# DAC.net
KiCad netlist of a schematic drawn in Altium Designer
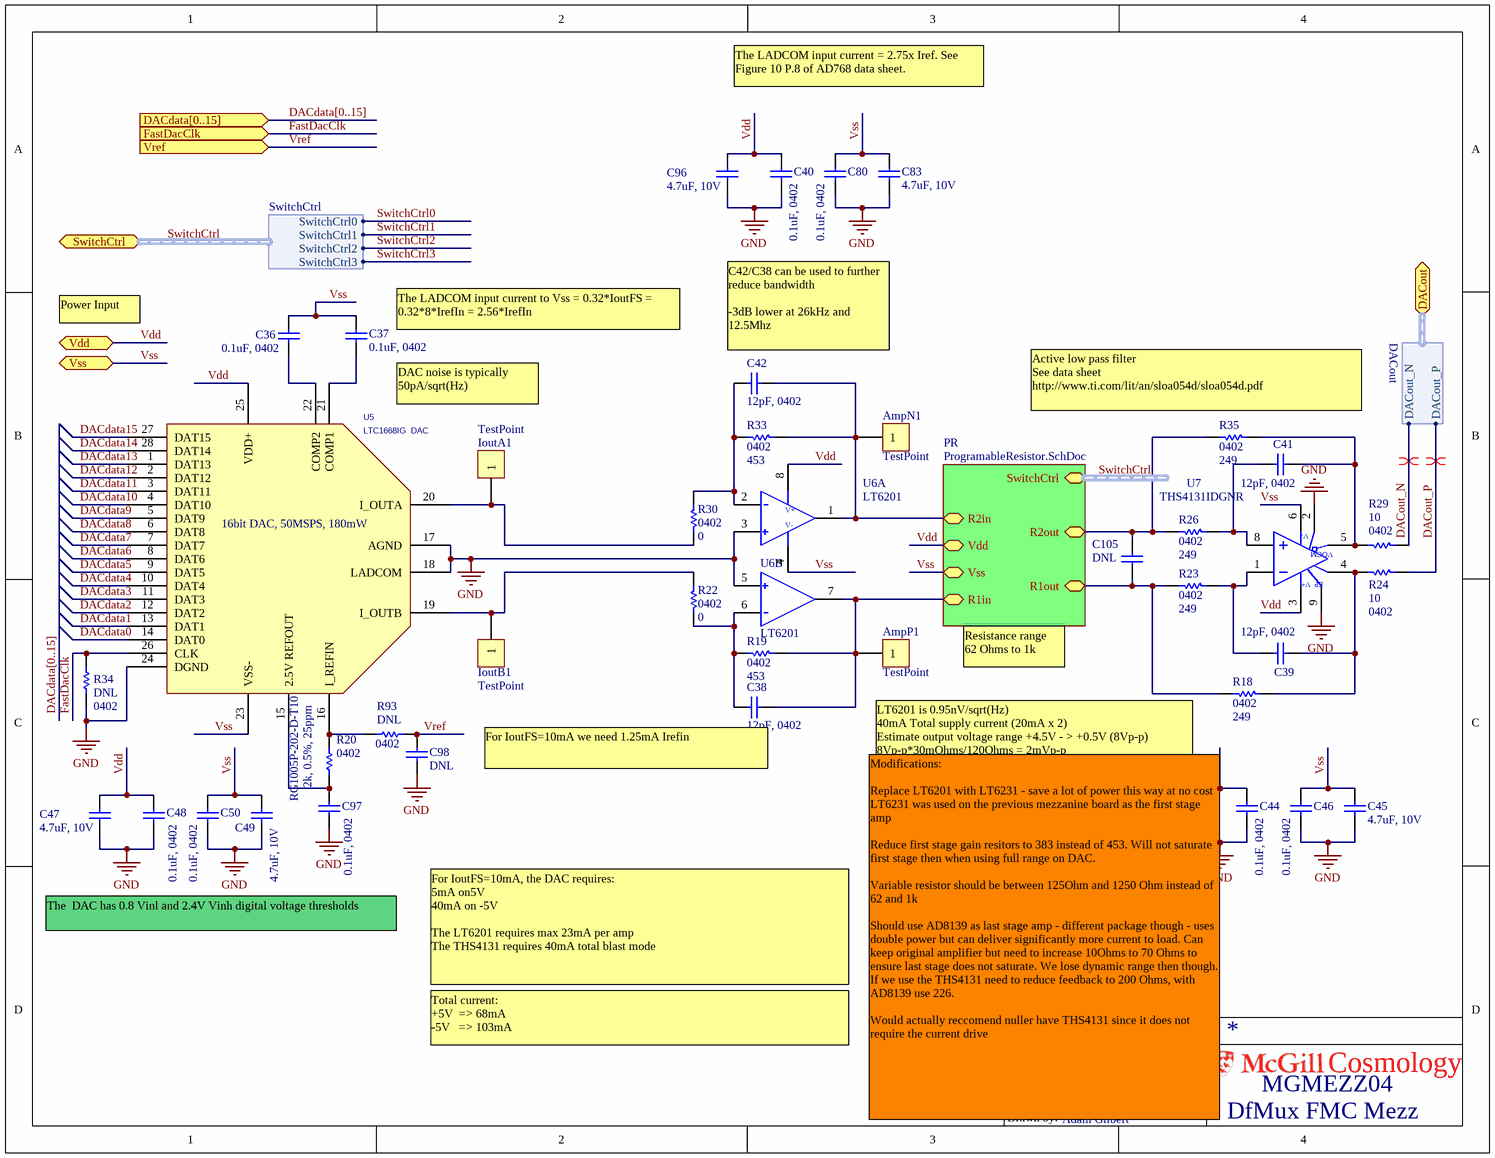
[diagram p0: DAC.SchDoc]

(export (version "E")
  (design (tool "Eeschema 10.0.6"))
  (components
    (comp (ref "AmpN1")
      (value "TestPoint")
      (footprint "TP-3520-SK")
      (description "TestPoint1")
      (libsource (lib "MGMEZZ04") (part "TestPoint"))
    )
    (comp (ref "AmpP1")
      (value "TestPoint")
      (footprint "TP-3520-SK")
      (description "TestPoint1")
      (libsource (lib "MGMEZZ04") (part "TestPoint"))
    )
    (comp (ref "C36")
      (value "0.1uF, 0402")
      (footprint "0402")
      (description "Capacitor, Ceramic, 0402")
      (fields (field (name "MANUFACTURER") "TDK Corporation"))
      (libsource (lib "MGMEZZ04") (part "CAP 0603"))
    )
    (comp (ref "C37")
      (value "0.1uF, 0402")
      (footprint "0402")
      (description "Capacitor, Ceramic, 0402")
      (fields (field (name "MANUFACTURER") "TDK Corporation"))
      (libsource (lib "MGMEZZ04") (part "CAP 0603"))
    )
    (comp (ref "C38")
      (value "12pF, 0402")
      (footprint "0402")
      (description "Capacitor, Ceramic, 0402")
      (fields (field (name "MANUFACTURER") "Generic"))
      (libsource (lib "MGMEZZ04") (part "CAP 0402"))
    )
    (comp (ref "C39")
      (value "12pF, 0402")
      (footprint "0402")
      (description "Capacitor, Ceramic, 0402")
      (fields (field (name "MANUFACTURER") "Generic"))
      (libsource (lib "MGMEZZ04") (part "CAP 0402"))
    )
    (comp (ref "C40")
      (value "0.1uF, 0402")
      (footprint "0402")
      (description "Capacitor, Ceramic, 0402")
      (fields (field (name "MANUFACTURER") "TDK Corporation"))
      (libsource (lib "MGMEZZ04") (part "CAP 0603"))
    )
    (comp (ref "C41")
      (value "12pF, 0402")
      (footprint "0402")
      (description "Capacitor, Ceramic, 0402")
      (fields (field (name "MANUFACTURER") "Generic"))
      (libsource (lib "MGMEZZ04") (part "CAP 0402"))
    )
    (comp (ref "C42")
      (value "12pF, 0402")
      (footprint "0402")
      (description "Capacitor, Ceramic, 0402")
      (fields (field (name "MANUFACTURER") "Generic"))
      (libsource (lib "MGMEZZ04") (part "CAP 0402"))
    )
    (comp (ref "C43")
      (value "4.7uF, 10V")
      (footprint "0805")
      (description "Capacitor, Ceramic, 0805")
      (fields (field (name "MANUFACTURER") "Taiyo Yuden"))
      (libsource (lib "MGMEZZ04") (part "CAP 0805"))
    )
    (comp (ref "C44")
      (value "0.1uF, 0402")
      (footprint "0402")
      (description "Capacitor, Ceramic, 0402")
      (fields (field (name "MANUFACTURER") "TDK Corporation"))
      (libsource (lib "MGMEZZ04") (part "CAP 0603"))
    )
    (comp (ref "C45")
      (value "4.7uF, 10V")
      (footprint "0805")
      (description "Capacitor, Ceramic, 0805")
      (fields (field (name "MANUFACTURER") "Taiyo Yuden"))
      (libsource (lib "MGMEZZ04") (part "CAP 0805"))
    )
    (comp (ref "C46")
      (value "0.1uF, 0402")
      (footprint "0402")
      (description "Capacitor, Ceramic, 0402")
      (fields (field (name "MANUFACTURER") "TDK Corporation"))
      (libsource (lib "MGMEZZ04") (part "CAP 0603"))
    )
    (comp (ref "C47")
      (value "4.7uF, 10V")
      (footprint "0805")
      (description "Capacitor, Ceramic, 0805")
      (fields (field (name "MANUFACTURER") "Taiyo Yuden"))
      (libsource (lib "MGMEZZ04") (part "CAP 0805"))
    )
    (comp (ref "C48")
      (value "0.1uF, 0402")
      (footprint "0402")
      (description "Capacitor, Ceramic, 0402")
      (fields (field (name "MANUFACTURER") "TDK Corporation"))
      (libsource (lib "MGMEZZ04") (part "CAP 0603"))
    )
    (comp (ref "C49")
      (value "4.7uF, 10V")
      (footprint "0805")
      (description "Capacitor, Ceramic, 0805")
      (fields (field (name "MANUFACTURER") "Taiyo Yuden"))
      (libsource (lib "MGMEZZ04") (part "CAP 0805"))
    )
    (comp (ref "C50")
      (value "0.1uF, 0402")
      (footprint "0402")
      (description "Capacitor, Ceramic, 0402")
      (fields (field (name "MANUFACTURER") "TDK Corporation"))
      (libsource (lib "MGMEZZ04") (part "CAP 0603"))
    )
    (comp (ref "C80")
      (value "0.1uF, 0402")
      (footprint "0402")
      (description "Capacitor, Ceramic, 0402")
      (fields (field (name "MANUFACTURER") "TDK Corporation"))
      (libsource (lib "MGMEZZ04") (part "CAP 0603"))
    )
    (comp (ref "C83")
      (value "4.7uF, 10V")
      (footprint "0805")
      (description "Capacitor, Ceramic, 0805")
      (fields (field (name "MANUFACTURER") "Taiyo Yuden"))
      (libsource (lib "MGMEZZ04") (part "CAP 0805"))
    )
    (comp (ref "C96")
      (value "4.7uF, 10V")
      (footprint "0805")
      (description "Capacitor, Ceramic, 0805")
      (fields (field (name "MANUFACTURER") "Taiyo Yuden"))
      (libsource (lib "MGMEZZ04") (part "CAP 0805"))
    )
    (comp (ref "C97")
      (value "0.1uF, 0402")
      (footprint "0402")
      (description "Capacitor, Ceramic, 0402")
      (fields (field (name "MANUFACTURER") "TDK Corporation"))
      (libsource (lib "MGMEZZ04") (part "CAP 0603"))
    )
    (comp (ref "C98")
      (value "DNL")
      (footprint "0805")
      (description "Capacitor, Ceramic, 0805")
      (fields (field (name "MANUFACTURER") "Taiyo Yuden"))
      (libsource (lib "MGMEZZ04") (part "CAP 0805"))
    )
    (comp (ref "C105")
      (value "DNL")
      (footprint "0402")
      (description "Capacitor, Ceramic, 0402")
      (fields (field (name "MANUFACTURER") "Generic"))
      (libsource (lib "MGMEZZ04") (part "CAP 0402"))
    )
    (comp (ref "IoutA1")
      (value "TestPoint")
      (footprint "TP-3520-SK")
      (description "TestPoint1")
      (libsource (lib "MGMEZZ04") (part "TestPoint"))
    )
    (comp (ref "IoutB1")
      (value "TestPoint")
      (footprint "TP-3520-SK")
      (description "TestPoint1")
      (libsource (lib "") (part "TestPoint_1"))
    )
    (comp (ref "R18")
      (value "249")
      (footprint "0402")
      (description "Resistor")
      (fields (field (name "MANUFACTURER") "Generic"))
      (libsource (lib "MGMEZZ04") (part "RES 0402"))
    )
    (comp (ref "R19")
      (value "453")
      (footprint "0402")
      (description "Resistor")
      (fields (field (name "MANUFACTURER") "Generic"))
      (libsource (lib "MGMEZZ04") (part "RES 0402"))
    )
    (comp (ref "R20")
      (value "2k, 0.5%, 25ppm")
      (footprint "0402")
      (description "Resistor")
      (fields
        (field (name "MANUFACTURER") "Susumu")
        (field (name "MANUFACTURER PART NUMBER 1") "RG1005P-202-D-T10")
      )
      (libsource (lib "MGMEZZ04") (part "RES 0402"))
    )
    (comp (ref "R22")
      (value "0")
      (footprint "0402")
      (description "Resistor")
      (fields (field (name "MANUFACTURER") "Generic"))
      (libsource (lib "MGMEZZ04") (part "RES 0402"))
    )
    (comp (ref "R23")
      (value "249")
      (footprint "0402")
      (description "Resistor")
      (fields (field (name "MANUFACTURER") "Generic"))
      (libsource (lib "MGMEZZ04") (part "RES 0402"))
    )
    (comp (ref "R24")
      (value "10")
      (footprint "0402")
      (description "Resistor")
      (fields (field (name "MANUFACTURER") "Generic"))
      (libsource (lib "MGMEZZ04") (part "RES 0402"))
    )
    (comp (ref "R26")
      (value "249")
      (footprint "0402")
      (description "Resistor")
      (fields (field (name "MANUFACTURER") "Generic"))
      (libsource (lib "MGMEZZ04") (part "RES 0402"))
    )
    (comp (ref "R29")
      (value "10")
      (footprint "0402")
      (description "Resistor")
      (fields (field (name "MANUFACTURER") "Generic"))
      (libsource (lib "MGMEZZ04") (part "RES 0402"))
    )
    (comp (ref "R30")
      (value "0")
      (footprint "0402")
      (description "Resistor")
      (fields (field (name "MANUFACTURER") "Generic"))
      (libsource (lib "MGMEZZ04") (part "RES 0402"))
    )
    (comp (ref "R33")
      (value "453")
      (footprint "0402")
      (description "Resistor")
      (fields (field (name "MANUFACTURER") "Generic"))
      (libsource (lib "MGMEZZ04") (part "RES 0402"))
    )
    (comp (ref "R34")
      (value "DNL")
      (footprint "0402")
      (description "Resistor")
      (fields (field (name "MANUFACTURER") "Generic"))
      (libsource (lib "MGMEZZ04") (part "RES 0402"))
    )
    (comp (ref "R35")
      (value "249")
      (footprint "0402")
      (description "Resistor")
      (fields (field (name "MANUFACTURER") "Generic"))
      (libsource (lib "MGMEZZ04") (part "RES 0402"))
    )
    (comp (ref "R93")
      (value "DNL")
      (footprint "0402")
      (description "Resistor")
      (fields (field (name "MANUFACTURER") "Susumu"))
      (libsource (lib "MGMEZZ04") (part "RES 0402"))
    )
    (comp (ref "U5")
      (value "LTC1668IG  DAC")
      (footprint "SOG.65M/28/WG8.20/L10.16")
      (description "IC DAC 16BIT 50MSPS 28SSOP")
      (fields (field (name "MANUFACTURER") "Linear Technology"))
      (libsource (lib "MGMEZZ04") (part "LTC1668IG  DAC"))
    )
    (comp (ref "U6")
      (value "LT6201")
      (footprint "SO8")
      (description "Dual R-R Opamp Soic 8 165Mhz GBP")
      (fields (field (name "MANUFACTURER") "Linear Technology"))
      (libsource (lib "MGMEZZ04") (part "LT6201"))
    )
    (comp (ref "U7")
      (value "THS4131IDGNR")
      (footprint "SOP8-EP-127P600-8N")
      (description "IC OPAMP DIFF 225MHZ SGL 8MSOP")
      (fields (field (name "MANUFACTURER") "Texas Instruments"))
      (libsource (lib "MGMEZZ04") (part "THS4131IDGNR"))
    )
  )
  (nets
    (net (code "4") (name "/DACdata0") (class "Default")
      (node (ref "U5") (pin "14") (pinfunction "DAT0_14") (pintype "passive"))
    )
    (net (code "5") (name "/DACdata1") (class "Default")
      (node (ref "U5") (pin "13") (pinfunction "DAT1_13") (pintype "passive"))
    )
    (net (code "6") (name "/DACdata2") (class "Default")
      (node (ref "U5") (pin "12") (pinfunction "DAT2_12") (pintype "passive"))
    )
    (net (code "7") (name "/DACdata3") (class "Default")
      (node (ref "U5") (pin "11") (pinfunction "DAT3_11") (pintype "passive"))
    )
    (net (code "8") (name "/DACdata4") (class "Default")
      (node (ref "U5") (pin "10") (pinfunction "DAT4_10") (pintype "passive"))
    )
    (net (code "9") (name "/DACdata5") (class "Default")
      (node (ref "U5") (pin "9") (pinfunction "DAT5_9") (pintype "passive"))
    )
    (net (code "10") (name "/DACdata6") (class "Default")
      (node (ref "U5") (pin "8") (pinfunction "DAT6_8") (pintype "passive"))
    )
    (net (code "11") (name "/DACdata7") (class "Default")
      (node (ref "U5") (pin "7") (pinfunction "DAT7_7") (pintype "passive"))
    )
    (net (code "12") (name "/DACdata8") (class "Default")
      (node (ref "U5") (pin "6") (pinfunction "DAT8_6") (pintype "passive"))
    )
    (net (code "13") (name "/DACdata9") (class "Default")
      (node (ref "U5") (pin "5") (pinfunction "DAT9_5") (pintype "passive"))
    )
    (net (code "14") (name "/DACdata10") (class "Default")
      (node (ref "U5") (pin "4") (pinfunction "DAT10_4") (pintype "passive"))
    )
    (net (code "15") (name "/DACdata11") (class "Default")
      (node (ref "U5") (pin "3") (pinfunction "DAT11_3") (pintype "passive"))
    )
    (net (code "16") (name "/DACdata12") (class "Default")
      (node (ref "U5") (pin "2") (pinfunction "DAT12_2") (pintype "passive"))
    )
    (net (code "17") (name "/DACdata13") (class "Default")
      (node (ref "U5") (pin "1") (pinfunction "DAT13_1") (pintype "passive"))
    )
    (net (code "18") (name "/DACdata14") (class "Default")
      (node (ref "U5") (pin "28") (pinfunction "DAT14_28") (pintype "passive"))
    )
    (net (code "19") (name "/DACdata15") (class "Default")
      (node (ref "U5") (pin "27") (pinfunction "DAT15_27") (pintype "passive"))
    )
    (net (code "21") (name "/DACout_N") (class "Default")
      (node (ref "R29") (pin "2") (pinfunction "2_2") (pintype "passive"))
    )
    (net (code "22") (name "/DACout_P") (class "Default")
      (node (ref "R24") (pin "2") (pinfunction "2_2") (pintype "passive"))
    )
    (net (code "23") (name "/FastDacClk") (class "Default")
      (node (ref "R34") (pin "2") (pinfunction "2_2") (pintype "passive"))
      (node (ref "U5") (pin "26") (pinfunction "CLK_26") (pintype "passive"))
    )
    (net (code "24") (name "/R1in") (class "Default")
      (node (ref "AmpP1") (pin "1") (pinfunction "1_1") (pintype "passive"))
      (node (ref "C38") (pin "1") (pinfunction "1_1") (pintype "passive"))
      (node (ref "R19") (pin "2") (pinfunction "2_2") (pintype "passive"))
      (node (ref "U6") (pin "7") (pinfunction "Out_7") (pintype "passive"))
    )
    (net (code "25") (name "/R1out") (class "Default")
      (node (ref "C105") (pin "2") (pinfunction "2_2") (pintype "passive"))
      (node (ref "R18") (pin "1") (pinfunction "1_1") (pintype "passive"))
      (node (ref "R23") (pin "1") (pinfunction "1_1") (pintype "passive"))
    )
    (net (code "26") (name "/R2in") (class "Default")
      (node (ref "AmpN1") (pin "1") (pinfunction "1_1") (pintype "passive"))
      (node (ref "C42") (pin "1") (pinfunction "1_1") (pintype "passive"))
      (node (ref "R33") (pin "2") (pinfunction "2_2") (pintype "passive"))
      (node (ref "U6") (pin "1") (pinfunction "Out_1") (pintype "passive"))
    )
    (net (code "27") (name "/R2out") (class "Default")
      (node (ref "C105") (pin "1") (pinfunction "1_1") (pintype "passive"))
      (node (ref "R26") (pin "1") (pinfunction "1_1") (pintype "passive"))
      (node (ref "R35") (pin "1") (pinfunction "1_1") (pintype "passive"))
    )
    (net (code "33") (name "/Vdd") (class "Default")
      (node (ref "C40") (pin "2") (pinfunction "2_2") (pintype "passive"))
      (node (ref "C43") (pin "2") (pinfunction "2_2") (pintype "passive"))
      (node (ref "C44") (pin "2") (pinfunction "2_2") (pintype "passive"))
      (node (ref "C47") (pin "2") (pinfunction "2_2") (pintype "passive"))
      (node (ref "C48") (pin "2") (pinfunction "2_2") (pintype "passive"))
      (node (ref "C96") (pin "2") (pinfunction "2_2") (pintype "passive"))
      (node (ref "U5") (pin "25") (pinfunction "VDD+_25") (pintype "passive"))
      (node (ref "U6") (pin "8") (pinfunction "V+_8") (pintype "power_in"))
      (node (ref "U7") (pin "3") (pinfunction "V+_3") (pintype "power_in"))
    )
    (net (code "34") (name "/Vref") (class "Default")
      (node (ref "C98") (pin "2") (pinfunction "2_2") (pintype "passive"))
      (node (ref "R93") (pin "1") (pinfunction "1_1") (pintype "passive"))
    )
    (net (code "35") (name "/Vss") (class "Default")
      (node (ref "C36") (pin "2") (pinfunction "2_2") (pintype "passive"))
      (node (ref "C37") (pin "2") (pinfunction "2_2") (pintype "passive"))
      (node (ref "C45") (pin "2") (pinfunction "2_2") (pintype "passive"))
      (node (ref "C46") (pin "2") (pinfunction "2_2") (pintype "passive"))
      (node (ref "C49") (pin "2") (pinfunction "2_2") (pintype "passive"))
      (node (ref "C50") (pin "2") (pinfunction "2_2") (pintype "passive"))
      (node (ref "C80") (pin "2") (pinfunction "2_2") (pintype "passive"))
      (node (ref "C83") (pin "2") (pinfunction "2_2") (pintype "passive"))
      (node (ref "U5") (pin "23") (pinfunction "VSS-_23") (pintype "passive"))
      (node (ref "U6") (pin "4") (pinfunction "V-_4") (pintype "power_in"))
      (node (ref "U7") (pin "6") (pinfunction "V-_6") (pintype "power_in"))
    )
    (net (code "38") (name "GND") (class "Default")
      (node (ref "C40") (pin "1") (pinfunction "1_1") (pintype "passive"))
      (node (ref "C43") (pin "1") (pinfunction "1_1") (pintype "passive"))
      (node (ref "C44") (pin "1") (pinfunction "1_1") (pintype "passive"))
      (node (ref "C45") (pin "1") (pinfunction "1_1") (pintype "passive"))
      (node (ref "C46") (pin "1") (pinfunction "1_1") (pintype "passive"))
      (node (ref "C47") (pin "1") (pinfunction "1_1") (pintype "passive"))
      (node (ref "C48") (pin "1") (pinfunction "1_1") (pintype "passive"))
      (node (ref "C49") (pin "1") (pinfunction "1_1") (pintype "passive"))
      (node (ref "C50") (pin "1") (pinfunction "1_1") (pintype "passive"))
      (node (ref "C80") (pin "1") (pinfunction "1_1") (pintype "passive"))
      (node (ref "C83") (pin "1") (pinfunction "1_1") (pintype "passive"))
      (node (ref "C96") (pin "1") (pinfunction "1_1") (pintype "passive"))
      (node (ref "C97") (pin "1") (pinfunction "1_1") (pintype "passive"))
      (node (ref "C98") (pin "1") (pinfunction "1_1") (pintype "passive"))
      (node (ref "R34") (pin "1") (pinfunction "1_1") (pintype "passive"))
      (node (ref "U5") (pin "17") (pinfunction "AGND_17") (pintype "passive"))
      (node (ref "U5") (pin "18") (pinfunction "LADCOM_18") (pintype "passive"))
      (node (ref "U5") (pin "24") (pinfunction "DGND_24") (pintype "passive"))
      (node (ref "U6") (pin "3") (pinfunction "IN+_3") (pintype "passive"))
      (node (ref "U6") (pin "5") (pinfunction "IN+_5") (pintype "passive"))
      (node (ref "U7") (pin "2") (pinfunction "VOCM_2") (pintype "passive"))
      (node (ref "U7") (pin "9") (pinfunction "EP_9") (pintype "power_in"))
    )
    (net (code "39") (name "Net-(U5-2.5V_REFOUT)") (class "Default")
      (node (ref "C97") (pin "2") (pinfunction "2_2") (pintype "passive"))
      (node (ref "R20") (pin "1") (pinfunction "1_1") (pintype "passive"))
      (node (ref "U5") (pin "15") (pinfunction "2.5V_REFOUT_15") (pintype "passive"))
    )
    (net (code "40") (name "Net-(U5-COMP1)") (class "Default")
      (node (ref "C37") (pin "1") (pinfunction "1_1") (pintype "passive"))
      (node (ref "U5") (pin "21") (pinfunction "COMP1_21") (pintype "passive"))
    )
    (net (code "41") (name "Net-(U5-COMP2)") (class "Default")
      (node (ref "C36") (pin "1") (pinfunction "1_1") (pintype "passive"))
      (node (ref "U5") (pin "22") (pinfunction "COMP2_22") (pintype "passive"))
    )
    (net (code "42") (name "Net-(U5-I_OUTA)") (class "Default")
      (node (ref "IoutA1") (pin "1") (pinfunction "1_1") (pintype "passive"))
      (node (ref "R30") (pin "1") (pinfunction "1_1") (pintype "passive"))
      (node (ref "U5") (pin "20") (pinfunction "I_OUTA_20") (pintype "passive"))
    )
    (net (code "43") (name "Net-(U5-I_OUTB)") (class "Default")
      (node (ref "IoutB1") (pin "1") (pinfunction "1_1") (pintype "passive"))
      (node (ref "R22") (pin "2") (pinfunction "2_2") (pintype "passive"))
      (node (ref "U5") (pin "19") (pinfunction "I_OUTB_19") (pintype "passive"))
    )
    (net (code "44") (name "Net-(U5-I_REFIN)") (class "Default")
      (node (ref "R20") (pin "2") (pinfunction "2_2") (pintype "passive"))
      (node (ref "R93") (pin "2") (pinfunction "2_2") (pintype "passive"))
      (node (ref "U5") (pin "16") (pinfunction "I_REFIN_16") (pintype "passive"))
    )
    (net (code "45") (name "Net-(U6A-IN-)") (class "Default")
      (node (ref "C42") (pin "2") (pinfunction "2_2") (pintype "passive"))
      (node (ref "R30") (pin "2") (pinfunction "2_2") (pintype "passive"))
      (node (ref "R33") (pin "1") (pinfunction "1_1") (pintype "passive"))
      (node (ref "U6") (pin "2") (pinfunction "IN-_2") (pintype "passive"))
    )
    (net (code "46") (name "Net-(U6B-IN-)") (class "Default")
      (node (ref "C38") (pin "2") (pinfunction "2_2") (pintype "passive"))
      (node (ref "R19") (pin "1") (pinfunction "1_1") (pintype "passive"))
      (node (ref "R22") (pin "1") (pinfunction "1_1") (pintype "passive"))
      (node (ref "U6") (pin "6") (pinfunction "IN-_6") (pintype "passive"))
    )
    (net (code "47") (name "Net-(U7-IN+)") (class "Default")
      (node (ref "C41") (pin "2") (pinfunction "2_2") (pintype "passive"))
      (node (ref "R26") (pin "2") (pinfunction "2_2") (pintype "passive"))
      (node (ref "U7") (pin "8") (pinfunction "IN+_8") (pintype "passive"))
    )
    (net (code "48") (name "Net-(U7-IN-)") (class "Default")
      (node (ref "C39") (pin "2") (pinfunction "2_2") (pintype "passive"))
      (node (ref "R23") (pin "2") (pinfunction "2_2") (pintype "passive"))
      (node (ref "U7") (pin "1") (pinfunction "IN-_1") (pintype "passive"))
    )
    (net (code "49") (name "Net-(U7-OUT+)") (class "Default")
      (node (ref "C39") (pin "1") (pinfunction "1_1") (pintype "passive"))
      (node (ref "R18") (pin "2") (pinfunction "2_2") (pintype "passive"))
      (node (ref "R24") (pin "1") (pinfunction "1_1") (pintype "passive"))
      (node (ref "U7") (pin "4") (pinfunction "OUT+_4") (pintype "passive"))
    )
    (net (code "50") (name "Net-(U7-OUT-)") (class "Default")
      (node (ref "C41") (pin "1") (pinfunction "1_1") (pintype "passive"))
      (node (ref "R29") (pin "1") (pinfunction "1_1") (pintype "passive"))
      (node (ref "R35") (pin "2") (pinfunction "2_2") (pintype "passive"))
      (node (ref "U7") (pin "5") (pinfunction "OUT-_5") (pintype "passive"))
    )
    (net (code "51") (name "unconnected-(U7-NC-Pad7)") (class "Default")
      (node (ref "U7") (pin "7") (pinfunction "NC_7") (pintype "passive"))
    )
  )
)
